# LRA_Driver.net
KiCad netlist of a schematic drawn in Altium Designer
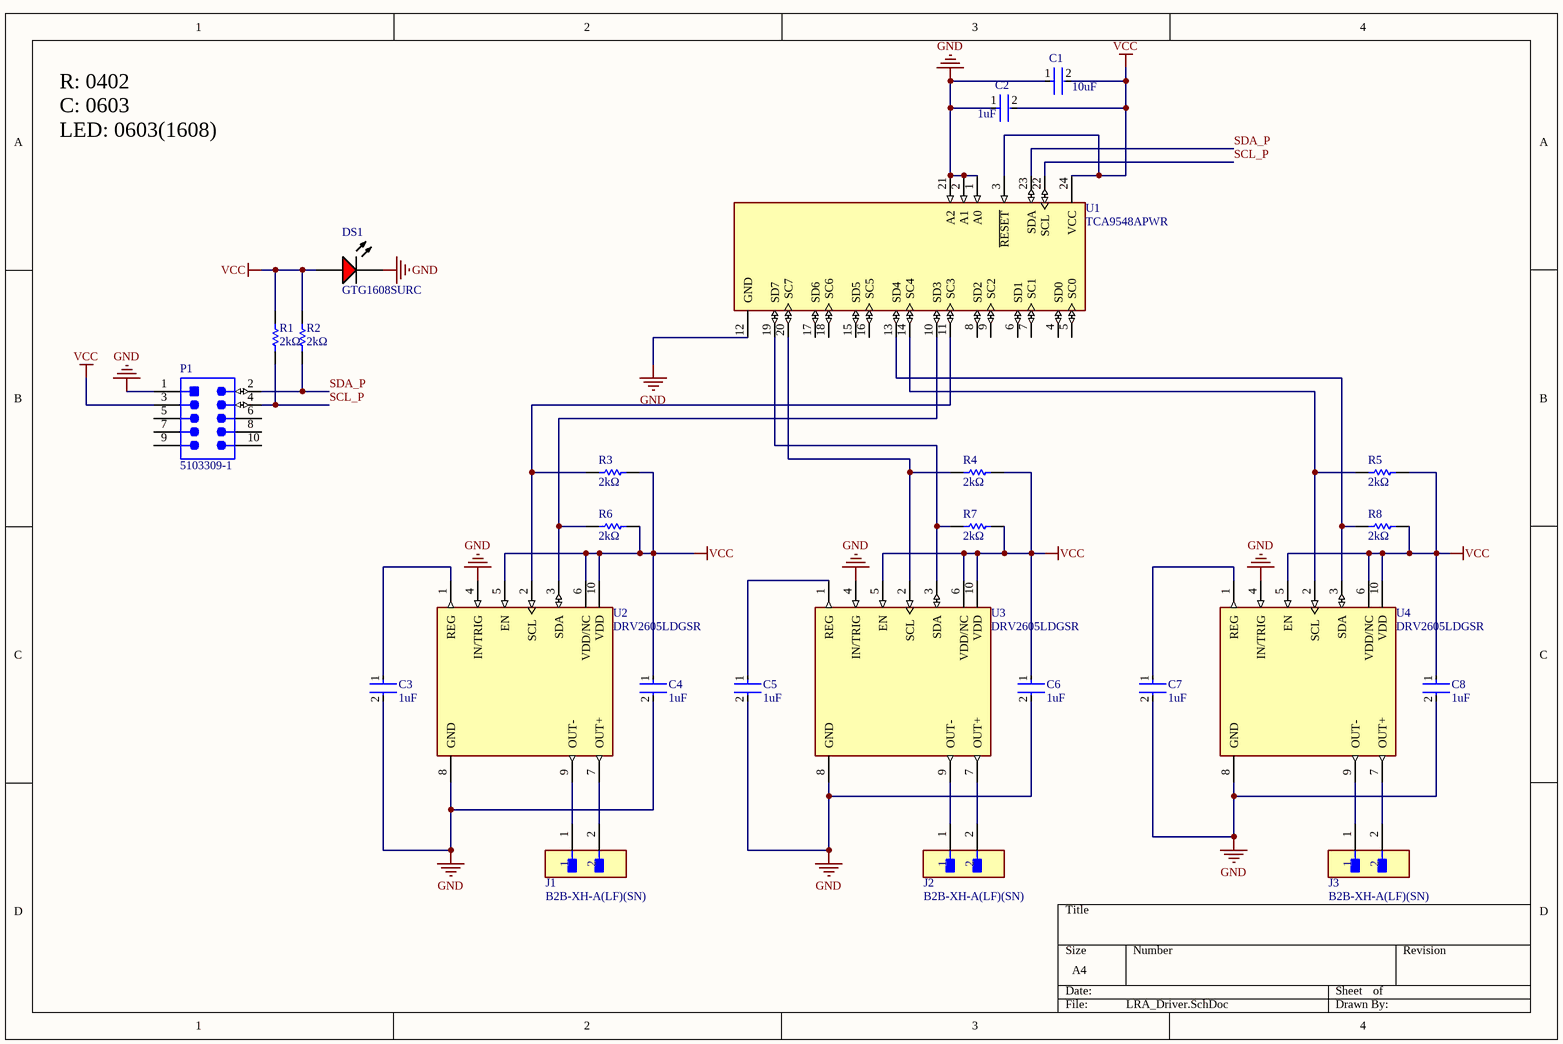
[diagram p0: LRA_Driver.SchDoc]

(export (version "E")
  (design (tool "Eeschema 10.0.6"))
  (components
    (comp (ref "C1")
      (value "10uF")
      (footprint "FP-0603-L_1_6_0_1-W_0_8_0-IPC_A")
      (description "0603")
      (fields (field (name "TOLERANCE") "10%"))
      (libsource (lib "Altium Content Vault") (part "11868f565c42a9108669ba33697ecf6"))
    )
    (comp (ref "C2")
      (value "1uF")
      (footprint "FP-0603-L_1_6_0_1-W_0_8_0-IPC_A")
      (description "0603")
      (fields (field (name "TOLERANCE") "10%"))
      (libsource (lib "Altium Content Vault") (part "11868f565c42a9108669ba33697ecf6"))
    )
    (comp (ref "C3")
      (value "1uF")
      (footprint "FP-0603-L_1_6_0_1-W_0_8_0-IPC_A")
      (description "0603")
      (fields (field (name "TOLERANCE") "10%"))
      (libsource (lib "Altium Content Vault") (part "11868f565c42a9108669ba33697ecf6"))
    )
    (comp (ref "C4")
      (value "1uF")
      (footprint "FP-0603-L_1_6_0_1-W_0_8_0-IPC_A")
      (description "0603")
      (fields (field (name "TOLERANCE") "10%"))
      (libsource (lib "Altium Content Vault") (part "11868f565c42a9108669ba33697ecf6"))
    )
    (comp (ref "C5")
      (value "1uF")
      (footprint "FP-0603-L_1_6_0_1-W_0_8_0-IPC_A")
      (description "0603")
      (fields (field (name "TOLERANCE") "10%"))
      (libsource (lib "Altium Content Vault") (part "11868f565c42a9108669ba33697ecf6"))
    )
    (comp (ref "C6")
      (value "1uF")
      (footprint "FP-0603-L_1_6_0_1-W_0_8_0-IPC_A")
      (description "0603")
      (fields (field (name "TOLERANCE") "10%"))
      (libsource (lib "Altium Content Vault") (part "11868f565c42a9108669ba33697ecf6"))
    )
    (comp (ref "C7")
      (value "1uF")
      (footprint "FP-0603-L_1_6_0_1-W_0_8_0-IPC_A")
      (description "0603")
      (fields (field (name "TOLERANCE") "10%"))
      (libsource (lib "Altium Content Vault") (part "11868f565c42a9108669ba33697ecf6"))
    )
    (comp (ref "C8")
      (value "1uF")
      (footprint "FP-0603-L_1_6_0_1-W_0_8_0-IPC_A")
      (description "0603")
      (fields (field (name "TOLERANCE") "10%"))
      (libsource (lib "Altium Content Vault") (part "11868f565c42a9108669ba33697ecf6"))
    )
    (comp (ref "DS1")
      (value "GTG1608SURC")
      (footprint "VISH-TLMS1000_V")
      (description "Low Current LED, 40 mW, 1.8 V, -40 to 100 degC, 2-Pin SMD (0603), RoHS, Tape and Reel")
      (fields (field (name "MANUFACTURER") "Vishay"))
      (libsource (lib "Altium Content Vault") (part "LED-RED-AK-2"))
    )
    (comp (ref "J1")
      (value "B2B-XH-A(LF)(SN)")
      (footprint "FP-B2B-XH-A_LF_SN-MFG")
      (description "CONN HEADER VERT 2POS 2.5MM")
      (libsource (lib "Altium Content Vault") (part "3bc925449376181038e59eaffc5286c"))
    )
    (comp (ref "J2")
      (value "B2B-XH-A(LF)(SN)")
      (footprint "FP-B2B-XH-A_LF_SN-MFG")
      (description "CONN HEADER VERT 2POS 2.5MM")
      (libsource (lib "Altium Content Vault") (part "3bc925449376181038e59eaffc5286c"))
    )
    (comp (ref "J3")
      (value "B2B-XH-A(LF)(SN)")
      (footprint "FP-B2B-XH-A_LF_SN-MFG")
      (description "CONN HEADER VERT 2POS 2.5MM")
      (libsource (lib "Altium Content Vault") (part "3bc925449376181038e59eaffc5286c"))
    )
    (comp (ref "P1")
      (value "5103309-1")
      (footprint "TECO-5103309-1_V")
      (fields (field (name "MANUFACTURER") "TE Connectivity"))
      (libsource (lib "Altium Content Vault") (part "CN-2P-M-R10"))
    )
    (comp (ref "R1")
      (value "2kΩ")
      (footprint "RESC1005X40X25ML10T10")
      (description "0402")
      (fields (field (name "MANUFACTURER") "Panasonic") (field (name "PART NUMBER") "ERA-2AEB202X"))
      (libsource (lib "Altium Content Vault") (part "RES"))
    )
    (comp (ref "R2")
      (value "2kΩ")
      (footprint "RESC1005X40X25ML10T10")
      (description "0402")
      (fields (field (name "MANUFACTURER") "Panasonic") (field (name "PART NUMBER") "ERA-2AEB202X"))
      (libsource (lib "Altium Content Vault") (part "RES"))
    )
    (comp (ref "R3")
      (value "2kΩ")
      (footprint "RESC1005X40X25ML10T10")
      (description "0402")
      (fields (field (name "MANUFACTURER") "Panasonic") (field (name "PART NUMBER") "ERA-2AEB202X"))
      (libsource (lib "Altium Content Vault") (part "RES"))
    )
    (comp (ref "R4")
      (value "2kΩ")
      (footprint "RESC1005X40X25ML10T10")
      (description "0402")
      (fields (field (name "MANUFACTURER") "Panasonic") (field (name "PART NUMBER") "ERA-2AEB202X"))
      (libsource (lib "Altium Content Vault") (part "RES"))
    )
    (comp (ref "R5")
      (value "2kΩ")
      (footprint "RESC1005X40X25ML10T10")
      (description "0402")
      (fields (field (name "MANUFACTURER") "Panasonic") (field (name "PART NUMBER") "ERA-2AEB202X"))
      (libsource (lib "Altium Content Vault") (part "RES"))
    )
    (comp (ref "R6")
      (value "2kΩ")
      (footprint "RESC1005X40X25ML10T10")
      (description "0402")
      (fields (field (name "MANUFACTURER") "Panasonic") (field (name "PART NUMBER") "ERA-2AEB202X"))
      (libsource (lib "Altium Content Vault") (part "RES"))
    )
    (comp (ref "R7")
      (value "2kΩ")
      (footprint "RESC1005X40X25ML10T10")
      (description "0402")
      (fields (field (name "MANUFACTURER") "Panasonic") (field (name "PART NUMBER") "ERA-2AEB202X"))
      (libsource (lib "Altium Content Vault") (part "RES"))
    )
    (comp (ref "R8")
      (value "2kΩ")
      (footprint "RESC1005X40X25ML10T10")
      (description "0402")
      (fields (field (name "MANUFACTURER") "Panasonic") (field (name "PART NUMBER") "ERA-2AEB202X"))
      (libsource (lib "Altium Content Vault") (part "RES"))
    )
    (comp (ref "U1")
      (value "TCA9548APWR")
      (footprint "FP-PW0024A-MFG")
      (description "IC I2C SW 8CH W/RESET 24TSSOP")
      (fields
        (field (name "MANUFACTURER") "Texas Instruments")
        (field (name "OCTOPART") "https://octopart.com/tca9548apwr-texas+instruments-22266789")
      )
      (libsource (lib "Altium Content Vault") (part "aab65143522579f0e88a32f493a4230"))
    )
    (comp (ref "U2")
      (value "DRV2605LDGSR")
      (footprint "FP-DGS0010A-MFG")
      (description "IC MOTOR DRIVER 2V-5.5V 10VSSOP")
      (libsource (lib "Altium Content Vault") (part "e4ad956cc5aa131d82cbc80a2fb1c90"))
    )
    (comp (ref "U3")
      (value "DRV2605LDGSR")
      (footprint "FP-DGS0010A-MFG")
      (description "IC MOTOR DRIVER 2V-5.5V 10VSSOP")
      (libsource (lib "Altium Content Vault") (part "e4ad956cc5aa131d82cbc80a2fb1c90"))
    )
    (comp (ref "U4")
      (value "DRV2605LDGSR")
      (footprint "FP-DGS0010A-MFG")
      (description "IC MOTOR DRIVER 2V-5.5V 10VSSOP")
      (libsource (lib "Altium Content Vault") (part "e4ad956cc5aa131d82cbc80a2fb1c90"))
    )
  )
  (nets
    (net (code "1") (name "/SCL_P") (class "Default")
      (node (ref "P1") (pin "4") (pinfunction "4_4") (pintype "bidirectional"))
      (node (ref "R1") (pin "2") (pinfunction "2_2") (pintype "passive"))
      (node (ref "U1") (pin "22") (pinfunction "SCL_22") (pintype "bidirectional"))
    )
    (net (code "2") (name "/SDA_P") (class "Default")
      (node (ref "P1") (pin "2") (pinfunction "2_2") (pintype "bidirectional"))
      (node (ref "R2") (pin "2") (pinfunction "2_2") (pintype "passive"))
      (node (ref "U1") (pin "23") (pinfunction "SDA_23") (pintype "bidirectional"))
    )
    (net (code "3") (name "GND") (class "Default")
      (node (ref "C1") (pin "1") (pinfunction "1_1") (pintype "passive"))
      (node (ref "C2") (pin "1") (pinfunction "1_1") (pintype "passive"))
      (node (ref "C3") (pin "2") (pinfunction "2_2") (pintype "passive"))
      (node (ref "C4") (pin "2") (pinfunction "2_2") (pintype "passive"))
      (node (ref "C5") (pin "2") (pinfunction "2_2") (pintype "passive"))
      (node (ref "C6") (pin "2") (pinfunction "2_2") (pintype "passive"))
      (node (ref "C7") (pin "2") (pinfunction "2_2") (pintype "passive"))
      (node (ref "C8") (pin "2") (pinfunction "2_2") (pintype "passive"))
      (node (ref "DS1") (pin "2") (pinfunction "K_2") (pintype "passive"))
      (node (ref "P1") (pin "1") (pinfunction "1_1") (pintype "power_in"))
      (node (ref "U1") (pin "1") (pinfunction "A0_1") (pintype "input"))
      (node (ref "U1") (pin "12") (pinfunction "GND_12") (pintype "power_in"))
      (node (ref "U1") (pin "2") (pinfunction "A1_2") (pintype "input"))
      (node (ref "U1") (pin "21") (pinfunction "A2_21") (pintype "input"))
      (node (ref "U2") (pin "4") (pinfunction "IN/TRIG_4") (pintype "input"))
      (node (ref "U2") (pin "8") (pinfunction "GND_8") (pintype "power_in"))
      (node (ref "U3") (pin "4") (pinfunction "IN/TRIG_4") (pintype "input"))
      (node (ref "U3") (pin "8") (pinfunction "GND_8") (pintype "power_in"))
      (node (ref "U4") (pin "4") (pinfunction "IN/TRIG_4") (pintype "input"))
      (node (ref "U4") (pin "8") (pinfunction "GND_8") (pintype "power_in"))
    )
    (net (code "4") (name "Net-(U1-SC3)") (class "Default")
      (node (ref "R3") (pin "2") (pinfunction "2_2") (pintype "passive"))
      (node (ref "U1") (pin "11") (pinfunction "SC3_11") (pintype "bidirectional"))
      (node (ref "U2") (pin "2") (pinfunction "SCL_2") (pintype "input"))
    )
    (net (code "5") (name "Net-(U1-SC4)") (class "Default")
      (node (ref "R5") (pin "2") (pinfunction "2_2") (pintype "passive"))
      (node (ref "U1") (pin "14") (pinfunction "SC4_14") (pintype "bidirectional"))
      (node (ref "U4") (pin "2") (pinfunction "SCL_2") (pintype "input"))
    )
    (net (code "6") (name "Net-(U1-SC7)") (class "Default")
      (node (ref "R4") (pin "2") (pinfunction "2_2") (pintype "passive"))
      (node (ref "U1") (pin "20") (pinfunction "SC7_20") (pintype "bidirectional"))
      (node (ref "U3") (pin "2") (pinfunction "SCL_2") (pintype "input"))
    )
    (net (code "7") (name "Net-(U1-SD3)") (class "Default")
      (node (ref "R6") (pin "2") (pinfunction "2_2") (pintype "passive"))
      (node (ref "U1") (pin "10") (pinfunction "SD3_10") (pintype "bidirectional"))
      (node (ref "U2") (pin "3") (pinfunction "SDA_3") (pintype "bidirectional"))
    )
    (net (code "8") (name "Net-(U1-SD4)") (class "Default")
      (node (ref "R8") (pin "2") (pinfunction "2_2") (pintype "passive"))
      (node (ref "U1") (pin "13") (pinfunction "SD4_13") (pintype "bidirectional"))
      (node (ref "U4") (pin "3") (pinfunction "SDA_3") (pintype "bidirectional"))
    )
    (net (code "9") (name "Net-(U1-SD7)") (class "Default")
      (node (ref "R7") (pin "2") (pinfunction "2_2") (pintype "passive"))
      (node (ref "U1") (pin "19") (pinfunction "SD7_19") (pintype "bidirectional"))
      (node (ref "U3") (pin "3") (pinfunction "SDA_3") (pintype "bidirectional"))
    )
    (net (code "10") (name "Net-(U2-OUT+)") (class "Default")
      (node (ref "J1") (pin "2") (pinfunction "2_2") (pintype "passive"))
      (node (ref "U2") (pin "7") (pinfunction "OUT+_7") (pintype "output"))
    )
    (net (code "11") (name "Net-(U2-OUT-)") (class "Default")
      (node (ref "J1") (pin "1") (pinfunction "1_1") (pintype "passive"))
      (node (ref "U2") (pin "9") (pinfunction "OUT-_9") (pintype "output"))
    )
    (net (code "12") (name "Net-(U2-REG)") (class "Default")
      (node (ref "C3") (pin "1") (pinfunction "1_1") (pintype "passive"))
      (node (ref "U2") (pin "1") (pinfunction "REG_1") (pintype "output"))
    )
    (net (code "13") (name "Net-(U3-OUT+)") (class "Default")
      (node (ref "J2") (pin "2") (pinfunction "2_2") (pintype "passive"))
      (node (ref "U3") (pin "7") (pinfunction "OUT+_7") (pintype "output"))
    )
    (net (code "14") (name "Net-(U3-OUT-)") (class "Default")
      (node (ref "J2") (pin "1") (pinfunction "1_1") (pintype "passive"))
      (node (ref "U3") (pin "9") (pinfunction "OUT-_9") (pintype "output"))
    )
    (net (code "15") (name "Net-(U3-REG)") (class "Default")
      (node (ref "C5") (pin "1") (pinfunction "1_1") (pintype "passive"))
      (node (ref "U3") (pin "1") (pinfunction "REG_1") (pintype "output"))
    )
    (net (code "16") (name "Net-(U4-OUT+)") (class "Default")
      (node (ref "J3") (pin "2") (pinfunction "2_2") (pintype "passive"))
      (node (ref "U4") (pin "7") (pinfunction "OUT+_7") (pintype "output"))
    )
    (net (code "17") (name "Net-(U4-OUT-)") (class "Default")
      (node (ref "J3") (pin "1") (pinfunction "1_1") (pintype "passive"))
      (node (ref "U4") (pin "9") (pinfunction "OUT-_9") (pintype "output"))
    )
    (net (code "18") (name "Net-(U4-REG)") (class "Default")
      (node (ref "C7") (pin "1") (pinfunction "1_1") (pintype "passive"))
      (node (ref "U4") (pin "1") (pinfunction "REG_1") (pintype "output"))
    )
    (net (code "19") (name "VCC") (class "Default")
      (node (ref "C1") (pin "2") (pinfunction "2_2") (pintype "passive"))
      (node (ref "C2") (pin "2") (pinfunction "2_2") (pintype "passive"))
      (node (ref "C4") (pin "1") (pinfunction "1_1") (pintype "passive"))
      (node (ref "C6") (pin "1") (pinfunction "1_1") (pintype "passive"))
      (node (ref "C8") (pin "1") (pinfunction "1_1") (pintype "passive"))
      (node (ref "DS1") (pin "1") (pinfunction "A_1") (pintype "passive"))
      (node (ref "P1") (pin "3") (pinfunction "3_3") (pintype "power_in"))
      (node (ref "R1") (pin "1") (pinfunction "1_1") (pintype "passive"))
      (node (ref "R2") (pin "1") (pinfunction "1_1") (pintype "passive"))
      (node (ref "R3") (pin "1") (pinfunction "1_1") (pintype "passive"))
      (node (ref "R4") (pin "1") (pinfunction "1_1") (pintype "passive"))
      (node (ref "R5") (pin "1") (pinfunction "1_1") (pintype "passive"))
      (node (ref "R6") (pin "1") (pinfunction "1_1") (pintype "passive"))
      (node (ref "R7") (pin "1") (pinfunction "1_1") (pintype "passive"))
      (node (ref "R8") (pin "1") (pinfunction "1_1") (pintype "passive"))
      (node (ref "U1") (pin "24") (pinfunction "VCC_24") (pintype "power_in"))
      (node (ref "U1") (pin "3") (pinfunction "~{RESET}_3") (pintype "input"))
      (node (ref "U2") (pin "10") (pinfunction "VDD_10") (pintype "power_in"))
      (node (ref "U2") (pin "5") (pinfunction "EN_5") (pintype "input"))
      (node (ref "U2") (pin "6") (pinfunction "VDD/NC_6") (pintype "power_in"))
      (node (ref "U3") (pin "10") (pinfunction "VDD_10") (pintype "power_in"))
      (node (ref "U3") (pin "5") (pinfunction "EN_5") (pintype "input"))
      (node (ref "U3") (pin "6") (pinfunction "VDD/NC_6") (pintype "power_in"))
      (node (ref "U4") (pin "10") (pinfunction "VDD_10") (pintype "power_in"))
      (node (ref "U4") (pin "5") (pinfunction "EN_5") (pintype "input"))
      (node (ref "U4") (pin "6") (pinfunction "VDD/NC_6") (pintype "power_in"))
    )
    (net (code "20") (name "unconnected-(P1-Pad5)") (class "Default")
      (node (ref "P1") (pin "5") (pinfunction "5_5") (pintype "passive"))
    )
    (net (code "21") (name "unconnected-(P1-Pad6)") (class "Default")
      (node (ref "P1") (pin "6") (pinfunction "6_6") (pintype "passive"))
    )
    (net (code "22") (name "unconnected-(P1-Pad7)") (class "Default")
      (node (ref "P1") (pin "7") (pinfunction "7_7") (pintype "passive"))
    )
    (net (code "23") (name "unconnected-(P1-Pad8)") (class "Default")
      (node (ref "P1") (pin "8") (pinfunction "8_8") (pintype "passive"))
    )
    (net (code "24") (name "unconnected-(P1-Pad9)") (class "Default")
      (node (ref "P1") (pin "9") (pinfunction "9_9") (pintype "passive"))
    )
    (net (code "25") (name "unconnected-(P1-Pad10)") (class "Default")
      (node (ref "P1") (pin "10") (pinfunction "10_10") (pintype "passive"))
    )
    (net (code "26") (name "unconnected-(U1-SC0-Pad5)") (class "Default")
      (node (ref "U1") (pin "5") (pinfunction "SC0_5") (pintype "bidirectional"))
    )
    (net (code "27") (name "unconnected-(U1-SC1-Pad7)") (class "Default")
      (node (ref "U1") (pin "7") (pinfunction "SC1_7") (pintype "bidirectional"))
    )
    (net (code "28") (name "unconnected-(U1-SC2-Pad9)") (class "Default")
      (node (ref "U1") (pin "9") (pinfunction "SC2_9") (pintype "bidirectional"))
    )
    (net (code "29") (name "unconnected-(U1-SC5-Pad16)") (class "Default")
      (node (ref "U1") (pin "16") (pinfunction "SC5_16") (pintype "bidirectional"))
    )
    (net (code "30") (name "unconnected-(U1-SC6-Pad18)") (class "Default")
      (node (ref "U1") (pin "18") (pinfunction "SC6_18") (pintype "bidirectional"))
    )
    (net (code "31") (name "unconnected-(U1-SD0-Pad4)") (class "Default")
      (node (ref "U1") (pin "4") (pinfunction "SD0_4") (pintype "bidirectional"))
    )
    (net (code "32") (name "unconnected-(U1-SD1-Pad6)") (class "Default")
      (node (ref "U1") (pin "6") (pinfunction "SD1_6") (pintype "bidirectional"))
    )
    (net (code "33") (name "unconnected-(U1-SD2-Pad8)") (class "Default")
      (node (ref "U1") (pin "8") (pinfunction "SD2_8") (pintype "bidirectional"))
    )
    (net (code "34") (name "unconnected-(U1-SD5-Pad15)") (class "Default")
      (node (ref "U1") (pin "15") (pinfunction "SD5_15") (pintype "bidirectional"))
    )
    (net (code "35") (name "unconnected-(U1-SD6-Pad17)") (class "Default")
      (node (ref "U1") (pin "17") (pinfunction "SD6_17") (pintype "bidirectional"))
    )
  )
)
